# lemidi.net
KiCad netlist of a schematic drawn in EAGLE
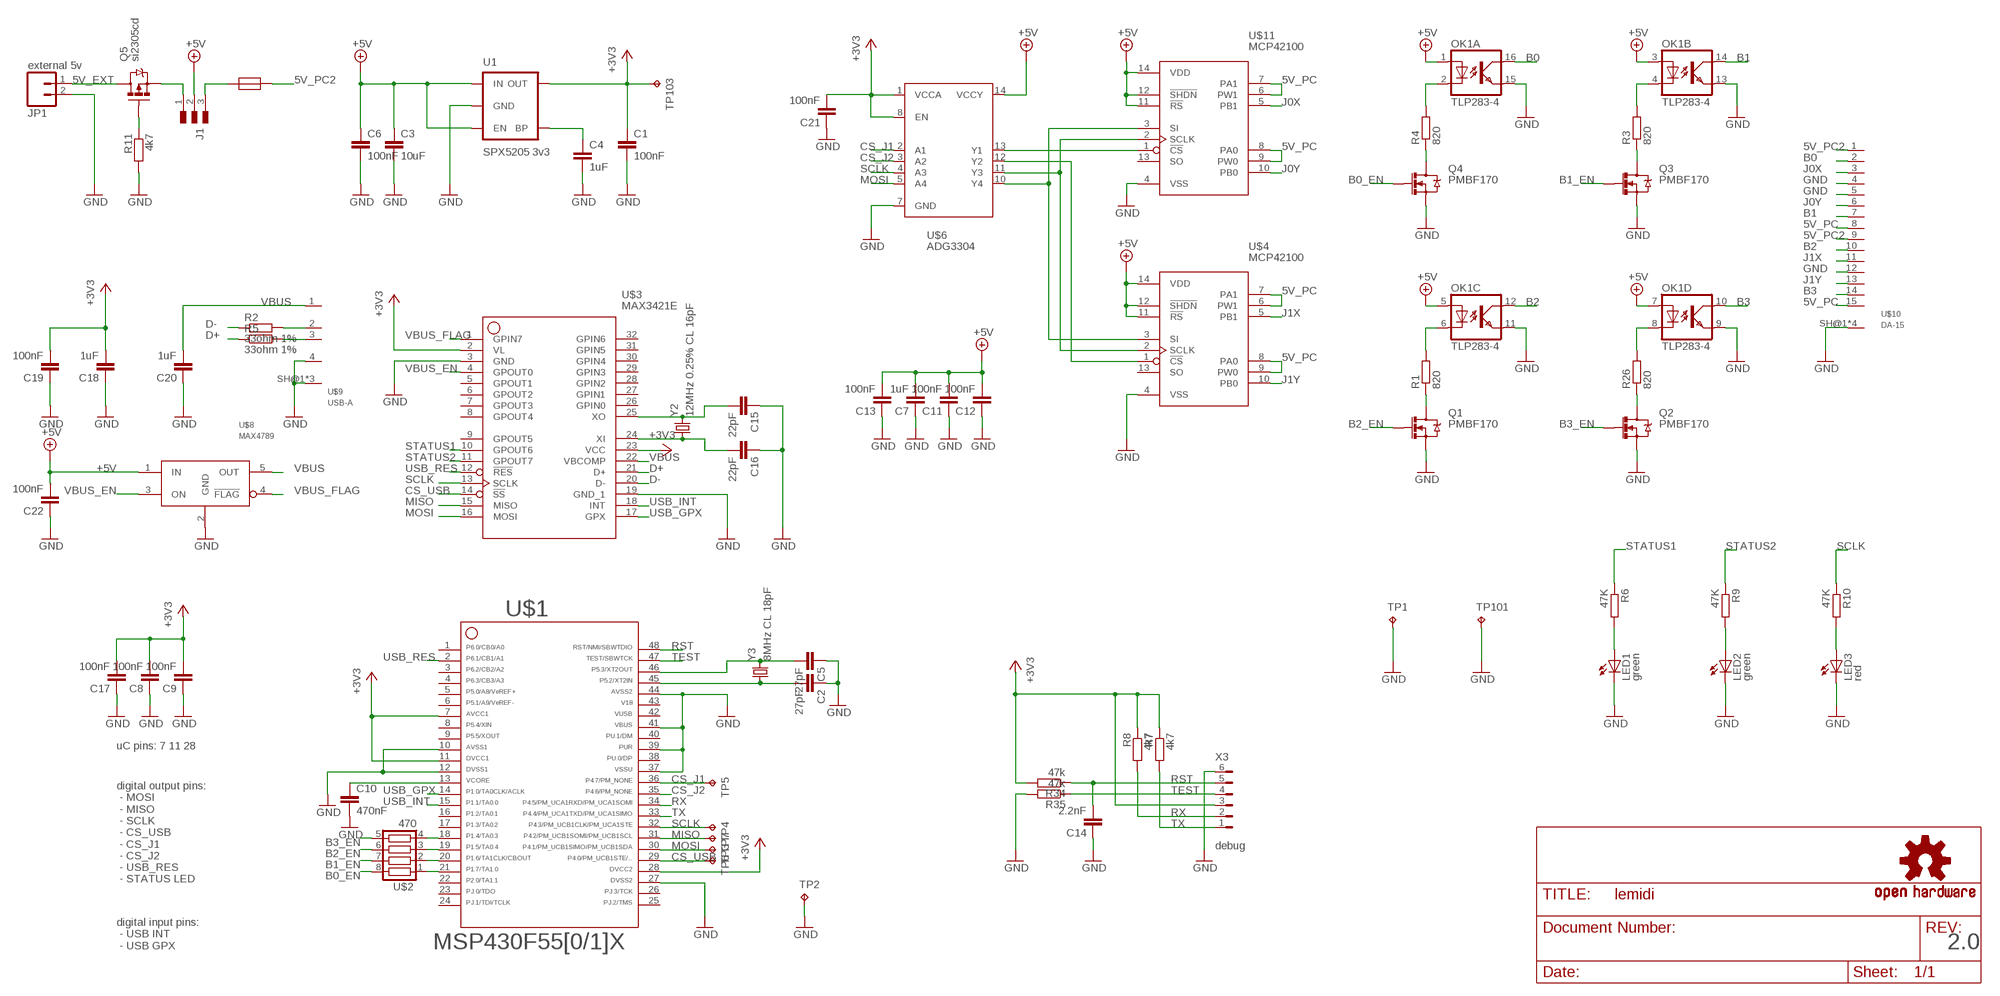
[diagram p0: schematic, sheet 1]

(export (version "E")
  (design (tool "Eeschema 10.0.6"))
  (components
    (comp (ref "C1")
      (value "100nF")
      (footprint "eagle-import:C0805")
      (libsource (lib "eagle-import") (part "C-EUC0805"))
    )
    (comp (ref "C2")
      (value "27pF")
      (footprint "eagle-import:C0805")
      (libsource (lib "eagle-import") (part "C-EUC0805"))
    )
    (comp (ref "C3")
      (value "10uF")
      (footprint "eagle-import:C0805")
      (libsource (lib "eagle-import") (part "C-EUC0805"))
    )
    (comp (ref "C4")
      (value "1uF")
      (footprint "eagle-import:C0805")
      (libsource (lib "eagle-import") (part "C-EUC0805"))
    )
    (comp (ref "C5")
      (value "27pF")
      (footprint "eagle-import:C0805")
      (libsource (lib "eagle-import") (part "C-EUC0805"))
    )
    (comp (ref "C6")
      (value "100nF")
      (footprint "eagle-import:C0805")
      (libsource (lib "eagle-import") (part "C-EUC0805"))
    )
    (comp (ref "C7")
      (value "1uF")
      (footprint "eagle-import:C0805")
      (libsource (lib "eagle-import") (part "C-EUC0805"))
    )
    (comp (ref "C8")
      (value "100nF")
      (footprint "eagle-import:C0805")
      (libsource (lib "eagle-import") (part "C-EUC0805"))
    )
    (comp (ref "C9")
      (value "100nF")
      (footprint "eagle-import:C0805")
      (libsource (lib "eagle-import") (part "C-EUC0805"))
    )
    (comp (ref "C10")
      (value "470nF")
      (footprint "eagle-import:C0805")
      (libsource (lib "eagle-import") (part "C-EUC0805"))
    )
    (comp (ref "C11")
      (value "100nF")
      (footprint "eagle-import:C0805")
      (libsource (lib "eagle-import") (part "C-EUC0805"))
    )
    (comp (ref "C12")
      (value "100nF")
      (footprint "eagle-import:C0805")
      (libsource (lib "eagle-import") (part "C-EUC0805"))
    )
    (comp (ref "C13")
      (value "100nF")
      (footprint "eagle-import:C0805")
      (libsource (lib "eagle-import") (part "C-EUC0805"))
    )
    (comp (ref "C14")
      (value "2.2nF")
      (footprint "eagle-import:C0805")
      (libsource (lib "eagle-import") (part "C-EUC0805"))
    )
    (comp (ref "C15")
      (value "22pF")
      (footprint "eagle-import:C0805")
      (libsource (lib "eagle-import") (part "C-EUC0805"))
    )
    (comp (ref "C16")
      (value "22pF")
      (footprint "eagle-import:C0805")
      (libsource (lib "eagle-import") (part "C-EUC0805"))
    )
    (comp (ref "C17")
      (value "100nF")
      (footprint "eagle-import:C0805")
      (libsource (lib "eagle-import") (part "C-EUC0805"))
    )
    (comp (ref "C18")
      (value "1uF")
      (footprint "eagle-import:C0805")
      (libsource (lib "eagle-import") (part "C-EUC0805"))
    )
    (comp (ref "C19")
      (value "100nF")
      (footprint "eagle-import:C0805")
      (libsource (lib "eagle-import") (part "C-EUC0805"))
    )
    (comp (ref "C20")
      (value "1uF")
      (footprint "eagle-import:C0805")
      (libsource (lib "eagle-import") (part "C-EUC0805"))
    )
    (comp (ref "C21")
      (value "100nF")
      (footprint "eagle-import:C0805")
      (libsource (lib "eagle-import") (part "C-EUC0805"))
    )
    (comp (ref "C22")
      (value "100nF")
      (footprint "eagle-import:C0805")
      (libsource (lib "eagle-import") (part "C-EUC0805"))
    )
    (comp (ref "J1")
      (value "SJ_3P")
      (footprint "eagle-import:SJ_3P")
      (libsource (lib "eagle-import") (part "SJ_3P"))
    )
    (comp (ref "JP1")
      (value "external 5v")
      (footprint "eagle-import:1X02")
      (libsource (lib "eagle-import") (part "M02PTH"))
    )
    (comp (ref "LED1")
      (value "green")
      (footprint "eagle-import:CHIPLED_0805")
      (libsource (lib "eagle-import") (part "LEDCHIPLED_0805"))
    )
    (comp (ref "LED2")
      (value "green")
      (footprint "eagle-import:CHIPLED_0805")
      (libsource (lib "eagle-import") (part "LEDCHIPLED_0805"))
    )
    (comp (ref "LED3")
      (value "red")
      (footprint "eagle-import:CHIPLED_0805")
      (libsource (lib "eagle-import") (part "LEDCHIPLED_0805"))
    )
    (comp (ref "OK1")
      (value "TLP283-4")
      (footprint "eagle-import:MINI-FLAT-16")
      (libsource (lib "eagle-import") (part "TLP283-4"))
    )
    (comp (ref "Q1")
      (value "PMBF170")
      (footprint "eagle-import:SOT23-3")
      (libsource (lib "eagle-import") (part "MOSFET-NCHANNEL_SOT23-3"))
    )
    (comp (ref "Q2")
      (value "PMBF170")
      (footprint "eagle-import:SOT23-3")
      (libsource (lib "eagle-import") (part "MOSFET-NCHANNEL_SOT23-3"))
    )
    (comp (ref "Q3")
      (value "PMBF170")
      (footprint "eagle-import:SOT23-3")
      (libsource (lib "eagle-import") (part "MOSFET-NCHANNEL_SOT23-3"))
    )
    (comp (ref "Q4")
      (value "PMBF170")
      (footprint "eagle-import:SOT23-3")
      (libsource (lib "eagle-import") (part "MOSFET-NCHANNEL_SOT23-3"))
    )
    (comp (ref "Q5")
      (value "si2305cd")
      (footprint "eagle-import:SOT23-3_POWER")
      (libsource (lib "eagle-import") (part "MOSFET-PCHANNELSMD_POWER"))
    )
    (comp (ref "R1")
      (value "820")
      (footprint "eagle-import:R0805W")
      (libsource (lib "eagle-import") (part "R-EU_R0805W"))
    )
    (comp (ref "R2")
      (value "33ohm 1%")
      (footprint "eagle-import:R0805W")
      (libsource (lib "eagle-import") (part "R-EU_R0805W"))
    )
    (comp (ref "R3")
      (value "820")
      (footprint "eagle-import:R0805W")
      (libsource (lib "eagle-import") (part "R-EU_R0805W"))
    )
    (comp (ref "R4")
      (value "820")
      (footprint "eagle-import:R0805W")
      (libsource (lib "eagle-import") (part "R-EU_R0805W"))
    )
    (comp (ref "R5")
      (value "33ohm 1%")
      (footprint "eagle-import:R0805W")
      (libsource (lib "eagle-import") (part "R-EU_R0805W"))
    )
    (comp (ref "R6")
      (value "47K")
      (footprint "eagle-import:R0805W")
      (libsource (lib "eagle-import") (part "R-EU_R0805W"))
    )
    (comp (ref "R7")
      (value "4k7")
      (footprint "eagle-import:R0805W")
      (libsource (lib "eagle-import") (part "R-EU_R0805W"))
    )
    (comp (ref "R8")
      (value "4k7")
      (footprint "eagle-import:R0805W")
      (libsource (lib "eagle-import") (part "R-EU_R0805W"))
    )
    (comp (ref "R9")
      (value "47K")
      (footprint "eagle-import:R0805W")
      (libsource (lib "eagle-import") (part "R-EU_R0805W"))
    )
    (comp (ref "R10")
      (value "47K")
      (footprint "eagle-import:R0805W")
      (libsource (lib "eagle-import") (part "R-EU_R0805W"))
    )
    (comp (ref "R11")
      (value "4k7")
      (footprint "eagle-import:R0805W")
      (libsource (lib "eagle-import") (part "R-EU_R0805W"))
    )
    (comp (ref "R26")
      (value "820")
      (footprint "eagle-import:R0805W")
      (libsource (lib "eagle-import") (part "R-EU_R0805W"))
    )
    (comp (ref "R34")
      (value "47k")
      (footprint "eagle-import:R0805W")
      (libsource (lib "eagle-import") (part "R-EU_R0805W"))
    )
    (comp (ref "R35")
      (value "47k")
      (footprint "eagle-import:R0805W")
      (libsource (lib "eagle-import") (part "R-EU_R0805W"))
    )
    (comp (ref "TP1")
      (value "TPTP12R")
      (footprint "eagle-import:TP12R")
      (libsource (lib "eagle-import") (part "TPTP12R"))
    )
    (comp (ref "TP2")
      (value "TPTP12R")
      (footprint "eagle-import:TP12R")
      (libsource (lib "eagle-import") (part "TPTP12R"))
    )
    (comp (ref "TP3")
      (value "TPTP12R")
      (footprint "eagle-import:TP12R")
      (libsource (lib "eagle-import") (part "TPTP12R"))
    )
    (comp (ref "TP4")
      (value "TPTP12R")
      (footprint "eagle-import:TP12R")
      (libsource (lib "eagle-import") (part "TPTP12R"))
    )
    (comp (ref "TP5")
      (value "TPTP12R")
      (footprint "eagle-import:TP12R")
      (libsource (lib "eagle-import") (part "TPTP12R"))
    )
    (comp (ref "TP6")
      (value "TPTP12R")
      (footprint "eagle-import:TP12R")
      (libsource (lib "eagle-import") (part "TPTP12R"))
    )
    (comp (ref "TP7")
      (value "TPTP12R")
      (footprint "eagle-import:TP12R")
      (libsource (lib "eagle-import") (part "TPTP12R"))
    )
    (comp (ref "TP101")
      (value "TPTP12R")
      (footprint "eagle-import:TP12R")
      (libsource (lib "eagle-import") (part "TPTP12R"))
    )
    (comp (ref "TP103")
      (value "TPTP12R")
      (footprint "eagle-import:TP12R")
      (libsource (lib "eagle-import") (part "TPTP12R"))
    )
    (comp (ref "U$1")
      (value "MSP430F5510")
      (footprint "eagle-import:PT48")
      (libsource (lib "eagle-import") (part "F55[0/1]X---PT48"))
    )
    (comp (ref "U$2")
      (value "470")
      (footprint "eagle-import:YC164")
      (libsource (lib "eagle-import") (part "RES_ARR"))
    )
    (comp (ref "U$3")
      (value "MAX3421E")
      (footprint "eagle-import:TQFP32")
      (libsource (lib "eagle-import") (part "MAX3421E"))
    )
    (comp (ref "U$4")
      (value "MCP42100")
      (footprint "eagle-import:SO-14")
      (libsource (lib "eagle-import") (part "MCP42XX"))
    )
    (comp (ref "U$6")
      (value "ADG3304")
      (footprint "eagle-import:TSSOP14")
      (libsource (lib "eagle-import") (part "ADG3304"))
    )
    (comp (ref "U$7")
      (value "OSHW-LOGOM")
      (footprint "eagle-import:OSHW-LOGO-M")
      (libsource (lib "eagle-import") (part "OSHW-LOGOM"))
    )
    (comp (ref "U$8")
      (value "MAX4789")
      (footprint "eagle-import:SOT23-5")
      (libsource (lib "eagle-import") (part "MAX4789"))
    )
    (comp (ref "U$9")
      (value "USB-A")
      (footprint "eagle-import:UBA-4R-D14T-4D")
      (libsource (lib "eagle-import") (part "UBA-4R-D14T-4D"))
    )
    (comp (ref "U$10")
      (value "DA-15")
      (footprint "eagle-import:ADAM_TECH_D-SUB_15")
      (libsource (lib "eagle-import") (part "ADAM_TECH-DSUB_DA-15"))
    )
    (comp (ref "U$11")
      (value "MCP42100")
      (footprint "eagle-import:SO-14")
      (libsource (lib "eagle-import") (part "MCP42XX"))
    )
    (comp (ref "U$12")
      (value "RESETTABLE_1210")
      (footprint "eagle-import:1210")
      (libsource (lib "eagle-import") (part "RESETTABLE_1210"))
    )
    (comp (ref "U1")
      (value "SPX5205 3v3")
      (footprint "eagle-import:SOT23-5")
      (libsource (lib "eagle-import") (part "V_REG_LDOSMD"))
    )
    (comp (ref "X3")
      (value "debug")
      (footprint "eagle-import:0530480610")
      (libsource (lib "eagle-import") (part "MOLEX_6HORIZONTAL"))
    )
    (comp (ref "Y2")
      (value "12MHz 0.25% CL 16pF")
      (footprint "eagle-import:CRYSTAL-SMD-11.4X4.35")
      (libsource (lib "eagle-import") (part "CRYSTAL"))
    )
    (comp (ref "Y3")
      (value "8MHz CL 18pF")
      (footprint "eagle-import:CRYSTAL-SMD-11.4X4.35")
      (libsource (lib "eagle-import") (part "CRYSTAL"))
    )
  )
  (nets
    (net (code "1") (name "+3V3") (class "Default")
      (node (ref "C1") (pin "1") (pinfunction "1_1") (pintype "passive"))
      (node (ref "C17") (pin "2") (pinfunction "2_2") (pintype "passive"))
      (node (ref "C18") (pin "2") (pinfunction "2_2") (pintype "passive"))
      (node (ref "C19") (pin "2") (pinfunction "2_2") (pintype "passive"))
      (node (ref "C21") (pin "2") (pinfunction "2_2") (pintype "passive"))
      (node (ref "C8") (pin "2") (pinfunction "2_2") (pintype "passive"))
      (node (ref "C9") (pin "2") (pinfunction "2_2") (pintype "passive"))
      (node (ref "R34") (pin "2") (pinfunction "2_2") (pintype "passive"))
      (node (ref "R7") (pin "1") (pinfunction "1_1") (pintype "passive"))
      (node (ref "R8") (pin "1") (pinfunction "1_1") (pintype "passive"))
      (node (ref "TP103") (pin "TP") (pinfunction "TP_TP") (pintype "input"))
      (node (ref "U$1") (pin "11") (pinfunction "11_11") (pintype "power_in"))
      (node (ref "U$1") (pin "28") (pinfunction "28_28") (pintype "power_in"))
      (node (ref "U$1") (pin "7") (pinfunction "7_7") (pintype "power_in"))
      (node (ref "U$3") (pin "2") (pinfunction "VL_2") (pintype "input"))
      (node (ref "U$3") (pin "23") (pinfunction "VCC_23") (pintype "bidirectional"))
      (node (ref "U$6") (pin "1") (pinfunction "VCCA_1") (pintype "bidirectional"))
      (node (ref "U$6") (pin "8") (pinfunction "EN_8") (pintype "bidirectional"))
      (node (ref "U1") (pin "5") (pinfunction "OUT_5") (pintype "passive"))
      (node (ref "X3") (pin "3") (pinfunction "4_3") (pintype "passive"))
    )
    (net (code "2") (name "+5V") (class "Default")
      (node (ref "C11") (pin "2") (pinfunction "2_2") (pintype "passive"))
      (node (ref "C12") (pin "2") (pinfunction "2_2") (pintype "passive"))
      (node (ref "C13") (pin "2") (pinfunction "2_2") (pintype "passive"))
      (node (ref "C22") (pin "2") (pinfunction "2_2") (pintype "passive"))
      (node (ref "C3") (pin "1") (pinfunction "1_1") (pintype "passive"))
      (node (ref "C6") (pin "1") (pinfunction "1_1") (pintype "passive"))
      (node (ref "C7") (pin "2") (pinfunction "2_2") (pintype "passive"))
      (node (ref "J1") (pin "2") (pinfunction "2_2") (pintype "passive"))
      (node (ref "OK1") (pin "1") (pinfunction "A_1") (pintype "passive"))
      (node (ref "OK1") (pin "3") (pinfunction "A_3") (pintype "passive"))
      (node (ref "OK1") (pin "5") (pinfunction "A_5") (pintype "passive"))
      (node (ref "OK1") (pin "7") (pinfunction "A_7") (pintype "passive"))
      (node (ref "U$11") (pin "11") (pinfunction "~{RS}_11") (pintype "bidirectional"))
      (node (ref "U$11") (pin "12") (pinfunction "~{SHDN}_12") (pintype "bidirectional"))
      (node (ref "U$11") (pin "14") (pinfunction "VDD_14") (pintype "bidirectional"))
      (node (ref "U$4") (pin "11") (pinfunction "~{RS}_11") (pintype "bidirectional"))
      (node (ref "U$4") (pin "12") (pinfunction "~{SHDN}_12") (pintype "bidirectional"))
      (node (ref "U$4") (pin "14") (pinfunction "VDD_14") (pintype "bidirectional"))
      (node (ref "U$6") (pin "14") (pinfunction "VCCY_14") (pintype "bidirectional"))
      (node (ref "U$8") (pin "1") (pinfunction "IN_1") (pintype "power_in"))
      (node (ref "U1") (pin "1") (pinfunction "IN_1") (pintype "input"))
      (node (ref "U1") (pin "3") (pinfunction "EN_3") (pintype "input"))
    )
    (net (code "3") (name "/5V_EXT") (class "Default")
      (node (ref "JP1") (pin "1") (pinfunction "1_1") (pintype "passive"))
      (node (ref "Q5") (pin "3") (pinfunction "D_3") (pintype "passive"))
    )
    (net (code "4") (name "/5V_PC") (class "Default")
      (node (ref "U$10") (pin "15") (pinfunction "15_15") (pintype "bidirectional"))
      (node (ref "U$10") (pin "8") (pinfunction "8_8") (pintype "bidirectional"))
      (node (ref "U$11") (pin "6") (pinfunction "PW1_6") (pintype "bidirectional"))
      (node (ref "U$11") (pin "7") (pinfunction "PA1_7") (pintype "bidirectional"))
      (node (ref "U$11") (pin "8") (pinfunction "PA0_8") (pintype "bidirectional"))
      (node (ref "U$11") (pin "9") (pinfunction "PW0_9") (pintype "bidirectional"))
      (node (ref "U$4") (pin "6") (pinfunction "PW1_6") (pintype "bidirectional"))
      (node (ref "U$4") (pin "7") (pinfunction "PA1_7") (pintype "bidirectional"))
      (node (ref "U$4") (pin "8") (pinfunction "PA0_8") (pintype "bidirectional"))
      (node (ref "U$4") (pin "9") (pinfunction "PW0_9") (pintype "bidirectional"))
    )
    (net (code "5") (name "/5V_PC2") (class "Default")
      (node (ref "U$10") (pin "1") (pinfunction "1_1") (pintype "bidirectional"))
      (node (ref "U$10") (pin "9") (pinfunction "9_9") (pintype "bidirectional"))
      (node (ref "U$12") (pin "P$2") (pinfunction "P$2_P$2") (pintype "bidirectional"))
    )
    (net (code "6") (name "/42") (class "Default")
      (node (ref "U$1") (pin "42") (pinfunction "42_42") (pintype "power_in"))
    )
    (net (code "7") (name "/43") (class "Default")
      (node (ref "U$1") (pin "43") (pinfunction "43_43") (pintype "power_in"))
    )
    (net (code "8") (name "/B0") (class "Default")
      (node (ref "OK1") (pin "16") (pinfunction "COL_16") (pintype "passive"))
      (node (ref "U$10") (pin "2") (pinfunction "2_2") (pintype "bidirectional"))
    )
    (net (code "9") (name "/B0_EN") (class "Default")
      (node (ref "Q4") (pin "1") (pinfunction "G_1") (pintype "passive"))
      (node (ref "U$2") (pin "8") (pinfunction "8_8") (pintype "passive"))
    )
    (net (code "10") (name "/B1") (class "Default")
      (node (ref "OK1") (pin "14") (pinfunction "COL_14") (pintype "passive"))
      (node (ref "U$10") (pin "7") (pinfunction "7_7") (pintype "bidirectional"))
    )
    (net (code "11") (name "/B1_EN") (class "Default")
      (node (ref "Q3") (pin "1") (pinfunction "G_1") (pintype "passive"))
      (node (ref "U$2") (pin "7") (pinfunction "7_7") (pintype "passive"))
    )
    (net (code "12") (name "/B2") (class "Default")
      (node (ref "OK1") (pin "12") (pinfunction "COL_12") (pintype "passive"))
      (node (ref "U$10") (pin "10") (pinfunction "10_10") (pintype "bidirectional"))
    )
    (net (code "13") (name "/B2_EN") (class "Default")
      (node (ref "Q1") (pin "1") (pinfunction "G_1") (pintype "passive"))
      (node (ref "U$2") (pin "6") (pinfunction "6_6") (pintype "passive"))
    )
    (net (code "14") (name "/B3") (class "Default")
      (node (ref "OK1") (pin "10") (pinfunction "COL_10") (pintype "passive"))
      (node (ref "U$10") (pin "14") (pinfunction "14_14") (pintype "bidirectional"))
    )
    (net (code "15") (name "/B3_EN") (class "Default")
      (node (ref "Q2") (pin "1") (pinfunction "G_1") (pintype "passive"))
      (node (ref "U$2") (pin "5") (pinfunction "5_5") (pintype "passive"))
    )
    (net (code "16") (name "/CS_J1") (class "Default")
      (node (ref "TP5") (pin "TP") (pinfunction "TP_TP") (pintype "input"))
      (node (ref "U$1") (pin "36") (pinfunction "36_36") (pintype "bidirectional"))
      (node (ref "U$6") (pin "2") (pinfunction "A1_2") (pintype "bidirectional"))
    )
    (net (code "17") (name "/CS_J2") (class "Default")
      (node (ref "U$1") (pin "35") (pinfunction "35_35") (pintype "bidirectional"))
      (node (ref "U$6") (pin "3") (pinfunction "A2_3") (pintype "bidirectional"))
    )
    (net (code "18") (name "/CS_USB") (class "Default")
      (node (ref "TP6") (pin "TP") (pinfunction "TP_TP") (pintype "input"))
      (node (ref "U$1") (pin "29") (pinfunction "29_29") (pintype "bidirectional"))
      (node (ref "U$3") (pin "14") (pinfunction "~{SS}_14") (pintype "input"))
    )
    (net (code "19") (name "/D+") (class "Default")
      (node (ref "R5") (pin "1") (pinfunction "1_1") (pintype "passive"))
      (node (ref "U$3") (pin "21") (pinfunction "D+_21") (pintype "bidirectional"))
    )
    (net (code "20") (name "/D-") (class "Default")
      (node (ref "R2") (pin "1") (pinfunction "1_1") (pintype "passive"))
      (node (ref "U$3") (pin "20") (pinfunction "D-_20") (pintype "bidirectional"))
    )
    (net (code "21") (name "/J0X") (class "Default")
      (node (ref "U$10") (pin "3") (pinfunction "3_3") (pintype "bidirectional"))
      (node (ref "U$11") (pin "5") (pinfunction "PB1_5") (pintype "bidirectional"))
    )
    (net (code "22") (name "/J0Y") (class "Default")
      (node (ref "U$10") (pin "6") (pinfunction "6_6") (pintype "bidirectional"))
      (node (ref "U$11") (pin "10") (pinfunction "PB0_10") (pintype "bidirectional"))
    )
    (net (code "23") (name "/J1X") (class "Default")
      (node (ref "U$10") (pin "11") (pinfunction "11_11") (pintype "bidirectional"))
      (node (ref "U$4") (pin "5") (pinfunction "PB1_5") (pintype "bidirectional"))
    )
    (net (code "24") (name "/J1Y") (class "Default")
      (node (ref "U$10") (pin "13") (pinfunction "13_13") (pintype "bidirectional"))
      (node (ref "U$4") (pin "10") (pinfunction "PB0_10") (pintype "bidirectional"))
    )
    (net (code "25") (name "/MISO") (class "Default")
      (node (ref "TP7") (pin "TP") (pinfunction "TP_TP") (pintype "input"))
      (node (ref "U$1") (pin "31") (pinfunction "31_31") (pintype "bidirectional"))
      (node (ref "U$3") (pin "15") (pinfunction "MISO_15") (pintype "output"))
    )
    (net (code "26") (name "/MOSI") (class "Default")
      (node (ref "TP3") (pin "TP") (pinfunction "TP_TP") (pintype "input"))
      (node (ref "U$1") (pin "30") (pinfunction "30_30") (pintype "bidirectional"))
      (node (ref "U$3") (pin "16") (pinfunction "MOSI_16") (pintype "bidirectional"))
      (node (ref "U$6") (pin "5") (pinfunction "A4_5") (pintype "bidirectional"))
    )
    (net (code "27") (name "/RST") (class "Default")
      (node (ref "C14") (pin "2") (pinfunction "2_2") (pintype "passive"))
      (node (ref "R34") (pin "1") (pinfunction "1_1") (pintype "passive"))
      (node (ref "U$1") (pin "48") (pinfunction "48_48") (pintype "bidirectional"))
      (node (ref "X3") (pin "5") (pinfunction "2_5") (pintype "passive"))
    )
    (net (code "28") (name "/RX") (class "Default")
      (node (ref "R8") (pin "2") (pinfunction "2_2") (pintype "passive"))
      (node (ref "U$1") (pin "34") (pinfunction "34_34") (pintype "bidirectional"))
      (node (ref "X3") (pin "2") (pinfunction "5_2") (pintype "passive"))
    )
    (net (code "29") (name "/SCLK") (class "Default")
      (node (ref "R10") (pin "1") (pinfunction "1_1") (pintype "passive"))
      (node (ref "TP4") (pin "TP") (pinfunction "TP_TP") (pintype "input"))
      (node (ref "U$1") (pin "32") (pinfunction "32_32") (pintype "bidirectional"))
      (node (ref "U$3") (pin "13") (pinfunction "SCLK_13") (pintype "input"))
      (node (ref "U$6") (pin "4") (pinfunction "A3_4") (pintype "bidirectional"))
    )
    (net (code "30") (name "/STATUS1") (class "Default")
      (node (ref "R6") (pin "1") (pinfunction "1_1") (pintype "passive"))
      (node (ref "U$3") (pin "10") (pinfunction "GPOUT6_10") (pintype "output"))
    )
    (net (code "31") (name "/STATUS2") (class "Default")
      (node (ref "R9") (pin "1") (pinfunction "1_1") (pintype "passive"))
      (node (ref "U$3") (pin "11") (pinfunction "GPOUT7_11") (pintype "output"))
    )
    (net (code "32") (name "/TEST") (class "Default")
      (node (ref "R35") (pin "1") (pinfunction "1_1") (pintype "passive"))
      (node (ref "U$1") (pin "47") (pinfunction "47_47") (pintype "input"))
      (node (ref "X3") (pin "4") (pinfunction "3_4") (pintype "passive"))
    )
    (net (code "33") (name "/TX") (class "Default")
      (node (ref "R7") (pin "2") (pinfunction "2_2") (pintype "passive"))
      (node (ref "U$1") (pin "33") (pinfunction "33_33") (pintype "bidirectional"))
      (node (ref "X3") (pin "1") (pinfunction "6_1") (pintype "passive"))
    )
    (net (code "34") (name "/USB_GPX") (class "Default")
      (node (ref "U$1") (pin "14") (pinfunction "14_14") (pintype "bidirectional"))
      (node (ref "U$3") (pin "17") (pinfunction "GPX_17") (pintype "output"))
    )
    (net (code "35") (name "/USB_INT") (class "Default")
      (node (ref "U$1") (pin "15") (pinfunction "15_15") (pintype "bidirectional"))
      (node (ref "U$3") (pin "18") (pinfunction "INT_18") (pintype "output"))
    )
    (net (code "36") (name "/USB_RES") (class "Default")
      (node (ref "U$1") (pin "2") (pinfunction "2_2") (pintype "bidirectional"))
      (node (ref "U$3") (pin "12") (pinfunction "~{RES}_12") (pintype "input"))
    )
    (net (code "37") (name "/VBUS") (class "Default")
      (node (ref "C20") (pin "2") (pinfunction "2_2") (pintype "passive"))
      (node (ref "U$3") (pin "22") (pinfunction "VBCOMP_22") (pintype "input"))
      (node (ref "U$8") (pin "5") (pinfunction "OUT_5") (pintype "power_in"))
      (node (ref "U$9") (pin "1") (pinfunction "1_1") (pintype "bidirectional"))
    )
    (net (code "38") (name "/VBUS_EN") (class "Default")
      (node (ref "U$3") (pin "4") (pinfunction "GPOUT0_4") (pintype "output"))
      (node (ref "U$8") (pin "3") (pinfunction "ON_3") (pintype "input"))
    )
    (net (code "39") (name "/VBUS_FLAG") (class "Default")
      (node (ref "U$3") (pin "1") (pinfunction "GPIN7_1") (pintype "input"))
      (node (ref "U$8") (pin "4") (pinfunction "~{FLAG}_4") (pintype "output"))
    )
    (net (code "40") (name "GND") (class "Default")
      (node (ref "C1") (pin "2") (pinfunction "2_2") (pintype "passive"))
      (node (ref "C10") (pin "2") (pinfunction "2_2") (pintype "passive"))
      (node (ref "C11") (pin "1") (pinfunction "1_1") (pintype "passive"))
      (node (ref "C12") (pin "1") (pinfunction "1_1") (pintype "passive"))
      (node (ref "C13") (pin "1") (pinfunction "1_1") (pintype "passive"))
      (node (ref "C14") (pin "1") (pinfunction "1_1") (pintype "passive"))
      (node (ref "C15") (pin "1") (pinfunction "1_1") (pintype "passive"))
      (node (ref "C16") (pin "1") (pinfunction "1_1") (pintype "passive"))
      (node (ref "C17") (pin "1") (pinfunction "1_1") (pintype "passive"))
      (node (ref "C18") (pin "1") (pinfunction "1_1") (pintype "passive"))
      (node (ref "C19") (pin "1") (pinfunction "1_1") (pintype "passive"))
      (node (ref "C2") (pin "1") (pinfunction "1_1") (pintype "passive"))
      (node (ref "C20") (pin "1") (pinfunction "1_1") (pintype "passive"))
      (node (ref "C21") (pin "1") (pinfunction "1_1") (pintype "passive"))
      (node (ref "C22") (pin "1") (pinfunction "1_1") (pintype "passive"))
      (node (ref "C3") (pin "2") (pinfunction "2_2") (pintype "passive"))
      (node (ref "C4") (pin "2") (pinfunction "2_2") (pintype "passive"))
      (node (ref "C5") (pin "1") (pinfunction "1_1") (pintype "passive"))
      (node (ref "C6") (pin "2") (pinfunction "2_2") (pintype "passive"))
      (node (ref "C7") (pin "1") (pinfunction "1_1") (pintype "passive"))
      (node (ref "C8") (pin "1") (pinfunction "1_1") (pintype "passive"))
      (node (ref "C9") (pin "1") (pinfunction "1_1") (pintype "passive"))
      (node (ref "JP1") (pin "2") (pinfunction "2_2") (pintype "passive"))
      (node (ref "LED1") (pin "C") (pinfunction "C_C") (pintype "passive"))
      (node (ref "LED2") (pin "C") (pinfunction "C_C") (pintype "passive"))
      (node (ref "LED3") (pin "C") (pinfunction "C_C") (pintype "passive"))
      (node (ref "OK1") (pin "11") (pinfunction "EMIT_11") (pintype "passive"))
      (node (ref "OK1") (pin "13") (pinfunction "EMIT_13") (pintype "passive"))
      (node (ref "OK1") (pin "15") (pinfunction "EMIT_15") (pintype "passive"))
      (node (ref "OK1") (pin "9") (pinfunction "EMIT_9") (pintype "passive"))
      (node (ref "Q1") (pin "2") (pinfunction "S_2") (pintype "passive"))
      (node (ref "Q2") (pin "2") (pinfunction "S_2") (pintype "passive"))
      (node (ref "Q3") (pin "2") (pinfunction "S_2") (pintype "passive"))
      (node (ref "Q4") (pin "2") (pinfunction "S_2") (pintype "passive"))
      (node (ref "R11") (pin "2") (pinfunction "2_2") (pintype "passive"))
      (node (ref "R35") (pin "2") (pinfunction "2_2") (pintype "passive"))
      (node (ref "TP1") (pin "TP") (pinfunction "TP_TP") (pintype "input"))
      (node (ref "TP101") (pin "TP") (pinfunction "TP_TP") (pintype "input"))
      (node (ref "TP2") (pin "TP") (pinfunction "TP_TP") (pintype "input"))
      (node (ref "U$1") (pin "10") (pinfunction "10_10") (pintype "power_in"))
      (node (ref "U$1") (pin "12") (pinfunction "12_12") (pintype "power_in"))
      (node (ref "U$1") (pin "27") (pinfunction "27_27") (pintype "power_in"))
      (node (ref "U$1") (pin "37") (pinfunction "37_37") (pintype "power_in"))
      (node (ref "U$1") (pin "39") (pinfunction "39_39") (pintype "bidirectional"))
      (node (ref "U$1") (pin "41") (pinfunction "41_41") (pintype "power_in"))
      (node (ref "U$1") (pin "44") (pinfunction "44_44") (pintype "power_in"))
      (node (ref "U$10") (pin "12") (pinfunction "12_12") (pintype "bidirectional"))
      (node (ref "U$10") (pin "4") (pinfunction "4_4") (pintype "bidirectional"))
      (node (ref "U$10") (pin "5") (pinfunction "5_5") (pintype "bidirectional"))
      (node (ref "U$10") (pin "SH@1") (pinfunction "SHIELD_SH@1") (pintype "bidirectional"))
      (node (ref "U$10") (pin "SH@2") (pinfunction "SHIELD_SH@2") (pintype "bidirectional"))
      (node (ref "U$10") (pin "SH@3") (pinfunction "SHIELD_SH@3") (pintype "bidirectional"))
      (node (ref "U$10") (pin "SH@4") (pinfunction "SHIELD_SH@4") (pintype "bidirectional"))
      (node (ref "U$11") (pin "4") (pinfunction "VSS_4") (pintype "bidirectional"))
      (node (ref "U$3") (pin "19") (pinfunction "GND_1_19") (pintype "bidirectional"))
      (node (ref "U$3") (pin "3") (pinfunction "GND_3") (pintype "bidirectional"))
      (node (ref "U$4") (pin "4") (pinfunction "VSS_4") (pintype "bidirectional"))
      (node (ref "U$6") (pin "7") (pinfunction "GND_7") (pintype "bidirectional"))
      (node (ref "U$8") (pin "2") (pinfunction "GND_2") (pintype "bidirectional"))
      (node (ref "U$9") (pin "4") (pinfunction "4_4") (pintype "bidirectional"))
      (node (ref "U$9") (pin "SH@1") (pinfunction "SH_SH@1") (pintype "bidirectional"))
      (node (ref "U$9") (pin "SH@2") (pinfunction "SH_SH@2") (pintype "bidirectional"))
      (node (ref "U$9") (pin "SH@3") (pinfunction "SH_SH@3") (pintype "bidirectional"))
      (node (ref "U1") (pin "2") (pinfunction "GND_2") (pintype "input"))
      (node (ref "X3") (pin "6") (pinfunction "1_6") (pintype "passive"))
    )
    (net (code "41") (name "Net-(C2-Pad2)") (class "Default")
      (node (ref "C2") (pin "2") (pinfunction "2_2") (pintype "passive"))
      (node (ref "U$1") (pin "45") (pinfunction "45_45") (pintype "bidirectional"))
      (node (ref "Y3") (pin "1") (pinfunction "1_1") (pintype "passive"))
    )
    (net (code "42") (name "Net-(C5-Pad2)") (class "Default")
      (node (ref "C5") (pin "2") (pinfunction "2_2") (pintype "passive"))
      (node (ref "U$1") (pin "46") (pinfunction "46_46") (pintype "power_in"))
      (node (ref "Y3") (pin "2") (pinfunction "2_2") (pintype "passive"))
    )
    (net (code "43") (name "Net-(C10-Pad1)") (class "Default")
      (node (ref "C10") (pin "1") (pinfunction "1_1") (pintype "passive"))
      (node (ref "U$1") (pin "13") (pinfunction "13_13") (pintype "power_in"))
    )
    (net (code "44") (name "Net-(J1-Pad3)") (class "Default")
      (node (ref "J1") (pin "3") (pinfunction "3_3") (pintype "passive"))
      (node (ref "U$12") (pin "P$1") (pinfunction "P$1_P$1") (pintype "bidirectional"))
    )
    (net (code "45") (name "Net-(LED1-PadA)") (class "Default")
      (node (ref "LED1") (pin "A") (pinfunction "A_A") (pintype "passive"))
      (node (ref "R6") (pin "2") (pinfunction "2_2") (pintype "passive"))
    )
    (net (code "46") (name "Net-(LED2-PadA)") (class "Default")
      (node (ref "LED2") (pin "A") (pinfunction "A_A") (pintype "passive"))
      (node (ref "R9") (pin "2") (pinfunction "2_2") (pintype "passive"))
    )
    (net (code "47") (name "Net-(LED3-PadA)") (class "Default")
      (node (ref "LED3") (pin "A") (pinfunction "A_A") (pintype "passive"))
      (node (ref "R10") (pin "2") (pinfunction "2_2") (pintype "passive"))
    )
    (net (code "48") (name "Net-(OK1A-C)") (class "Default")
      (node (ref "OK1") (pin "2") (pinfunction "C_2") (pintype "passive"))
      (node (ref "R4") (pin "2") (pinfunction "2_2") (pintype "passive"))
    )
    (net (code "49") (name "Net-(OK1B-C)") (class "Default")
      (node (ref "OK1") (pin "4") (pinfunction "C_4") (pintype "passive"))
      (node (ref "R3") (pin "2") (pinfunction "2_2") (pintype "passive"))
    )
    (net (code "50") (name "Net-(OK1C-C)") (class "Default")
      (node (ref "OK1") (pin "6") (pinfunction "C_6") (pintype "passive"))
      (node (ref "R1") (pin "2") (pinfunction "2_2") (pintype "passive"))
    )
    (net (code "51") (name "Net-(OK1D-C)") (class "Default")
      (node (ref "OK1") (pin "8") (pinfunction "C_8") (pintype "passive"))
      (node (ref "R26") (pin "2") (pinfunction "2_2") (pintype "passive"))
    )
    (net (code "52") (name "Net-(Q1-D)") (class "Default")
      (node (ref "Q1") (pin "3") (pinfunction "D_3") (pintype "passive"))
      (node (ref "R1") (pin "1") (pinfunction "1_1") (pintype "passive"))
    )
    (net (code "53") (name "Net-(Q2-D)") (class "Default")
      (node (ref "Q2") (pin "3") (pinfunction "D_3") (pintype "passive"))
      (node (ref "R26") (pin "1") (pinfunction "1_1") (pintype "passive"))
    )
    (net (code "54") (name "Net-(Q3-D)") (class "Default")
      (node (ref "Q3") (pin "3") (pinfunction "D_3") (pintype "passive"))
      (node (ref "R3") (pin "1") (pinfunction "1_1") (pintype "passive"))
    )
    (net (code "55") (name "Net-(Q4-D)") (class "Default")
      (node (ref "Q4") (pin "3") (pinfunction "D_3") (pintype "passive"))
      (node (ref "R4") (pin "1") (pinfunction "1_1") (pintype "passive"))
    )
    (net (code "56") (name "Net-(Q5-G)") (class "Default")
      (node (ref "Q5") (pin "1") (pinfunction "G_1") (pintype "passive"))
      (node (ref "R11") (pin "1") (pinfunction "1_1") (pintype "passive"))
    )
    (net (code "57") (name "Net-(Q5-S)") (class "Default")
      (node (ref "J1") (pin "1") (pinfunction "1_1") (pintype "passive"))
      (node (ref "Q5") (pin "2") (pinfunction "S_2") (pintype "passive"))
    )
    (net (code "58") (name "Net-(R2-Pad2)") (class "Default")
      (node (ref "R2") (pin "2") (pinfunction "2_2") (pintype "passive"))
      (node (ref "U$9") (pin "2") (pinfunction "2_2") (pintype "bidirectional"))
    )
    (net (code "59") (name "Net-(R5-Pad2)") (class "Default")
      (node (ref "R5") (pin "2") (pinfunction "2_2") (pintype "passive"))
      (node (ref "U$9") (pin "3") (pinfunction "3_3") (pintype "bidirectional"))
    )
    (net (code "60") (name "Net-(U$1-Pad18)") (class "Default")
      (node (ref "U$1") (pin "18") (pinfunction "18_18") (pintype "bidirectional"))
      (node (ref "U$2") (pin "4") (pinfunction "4_4") (pintype "passive"))
    )
    (net (code "61") (name "Net-(U$1-Pad19)") (class "Default")
      (node (ref "U$1") (pin "19") (pinfunction "19_19") (pintype "bidirectional"))
      (node (ref "U$2") (pin "3") (pinfunction "3_3") (pintype "passive"))
    )
    (net (code "62") (name "Net-(U$1-Pad20)") (class "Default")
      (node (ref "U$1") (pin "20") (pinfunction "20_20") (pintype "bidirectional"))
      (node (ref "U$2") (pin "2") (pinfunction "2_2") (pintype "passive"))
    )
    (net (code "63") (name "Net-(U$1-Pad21)") (class "Default")
      (node (ref "U$1") (pin "21") (pinfunction "21_21") (pintype "bidirectional"))
      (node (ref "U$2") (pin "1") (pinfunction "1_1") (pintype "passive"))
    )
    (net (code "64") (name "Net-(U$3-XI)") (class "Default")
      (node (ref "C16") (pin "2") (pinfunction "2_2") (pintype "passive"))
      (node (ref "U$3") (pin "24") (pinfunction "XI_24") (pintype "input"))
      (node (ref "Y2") (pin "1") (pinfunction "1_1") (pintype "passive"))
    )
    (net (code "65") (name "Net-(U$3-XO)") (class "Default")
      (node (ref "C15") (pin "2") (pinfunction "2_2") (pintype "passive"))
      (node (ref "U$3") (pin "25") (pinfunction "XO_25") (pintype "output"))
      (node (ref "Y2") (pin "2") (pinfunction "2_2") (pintype "passive"))
    )
    (net (code "66") (name "Net-(U$4-~{CS})") (class "Default")
      (node (ref "U$4") (pin "1") (pinfunction "~{CS}_1") (pintype "input"))
      (node (ref "U$6") (pin "12") (pinfunction "Y2_12") (pintype "bidirectional"))
    )
    (net (code "67") (name "Net-(U$11-SCLK)") (class "Default")
      (node (ref "U$11") (pin "2") (pinfunction "SCLK_2") (pintype "input"))
      (node (ref "U$4") (pin "2") (pinfunction "SCLK_2") (pintype "input"))
      (node (ref "U$6") (pin "11") (pinfunction "Y3_11") (pintype "bidirectional"))
    )
    (net (code "68") (name "Net-(U$11-SI)") (class "Default")
      (node (ref "U$11") (pin "3") (pinfunction "SI_3") (pintype "input"))
      (node (ref "U$4") (pin "3") (pinfunction "SI_3") (pintype "input"))
      (node (ref "U$6") (pin "10") (pinfunction "Y4_10") (pintype "bidirectional"))
    )
    (net (code "69") (name "Net-(U$11-~{CS})") (class "Default")
      (node (ref "U$11") (pin "1") (pinfunction "~{CS}_1") (pintype "input"))
      (node (ref "U$6") (pin "13") (pinfunction "Y1_13") (pintype "bidirectional"))
    )
    (net (code "70") (name "Net-(U1-BP)") (class "Default")
      (node (ref "C4") (pin "1") (pinfunction "1_1") (pintype "passive"))
      (node (ref "U1") (pin "4") (pinfunction "BP_4") (pintype "input"))
    )
    (net (code "71") (name "unconnected-(U$1-Pad1)") (class "Default")
      (node (ref "U$1") (pin "1") (pinfunction "1_1") (pintype "bidirectional"))
    )
    (net (code "72") (name "unconnected-(U$1-Pad3)") (class "Default")
      (node (ref "U$1") (pin "3") (pinfunction "3_3") (pintype "bidirectional"))
    )
    (net (code "73") (name "unconnected-(U$1-Pad4)") (class "Default")
      (node (ref "U$1") (pin "4") (pinfunction "4_4") (pintype "bidirectional"))
    )
    (net (code "74") (name "unconnected-(U$1-Pad5)") (class "Default")
      (node (ref "U$1") (pin "5") (pinfunction "5_5") (pintype "bidirectional"))
    )
    (net (code "75") (name "unconnected-(U$1-Pad6)") (class "Default")
      (node (ref "U$1") (pin "6") (pinfunction "6_6") (pintype "bidirectional"))
    )
    (net (code "76") (name "unconnected-(U$1-Pad8)") (class "Default")
      (node (ref "U$1") (pin "8") (pinfunction "8_8") (pintype "bidirectional"))
    )
    (net (code "77") (name "unconnected-(U$1-Pad9)") (class "Default")
      (node (ref "U$1") (pin "9") (pinfunction "9_9") (pintype "bidirectional"))
    )
    (net (code "78") (name "unconnected-(U$1-Pad16)") (class "Default")
      (node (ref "U$1") (pin "16") (pinfunction "16_16") (pintype "bidirectional"))
    )
    (net (code "79") (name "unconnected-(U$1-Pad17)") (class "Default")
      (node (ref "U$1") (pin "17") (pinfunction "17_17") (pintype "bidirectional"))
    )
    (net (code "80") (name "unconnected-(U$1-Pad22)") (class "Default")
      (node (ref "U$1") (pin "22") (pinfunction "22_22") (pintype "bidirectional"))
    )
    (net (code "81") (name "unconnected-(U$1-Pad23)") (class "Default")
      (node (ref "U$1") (pin "23") (pinfunction "23_23") (pintype "bidirectional"))
    )
    (net (code "82") (name "unconnected-(U$1-Pad24)") (class "Default")
      (node (ref "U$1") (pin "24") (pinfunction "24_24") (pintype "bidirectional"))
    )
    (net (code "83") (name "unconnected-(U$1-Pad25)") (class "Default")
      (node (ref "U$1") (pin "25") (pinfunction "25_25") (pintype "bidirectional"))
    )
    (net (code "84") (name "unconnected-(U$1-Pad26)") (class "Default")
      (node (ref "U$1") (pin "26") (pinfunction "26_26") (pintype "bidirectional"))
    )
    (net (code "85") (name "unconnected-(U$1-Pad38)") (class "Default")
      (node (ref "U$1") (pin "38") (pinfunction "38_38") (pintype "bidirectional"))
    )
    (net (code "86") (name "unconnected-(U$1-Pad40)") (class "Default")
      (node (ref "U$1") (pin "40") (pinfunction "40_40") (pintype "bidirectional"))
    )
    (net (code "87") (name "unconnected-(U$3-GPIN0-Pad26)") (class "Default")
      (node (ref "U$3") (pin "26") (pinfunction "GPIN0_26") (pintype "input"))
    )
    (net (code "88") (name "unconnected-(U$3-GPIN1-Pad27)") (class "Default")
      (node (ref "U$3") (pin "27") (pinfunction "GPIN1_27") (pintype "input"))
    )
    (net (code "89") (name "unconnected-(U$3-GPIN2-Pad28)") (class "Default")
      (node (ref "U$3") (pin "28") (pinfunction "GPIN2_28") (pintype "input"))
    )
    (net (code "90") (name "unconnected-(U$3-GPIN3-Pad29)") (class "Default")
      (node (ref "U$3") (pin "29") (pinfunction "GPIN3_29") (pintype "input"))
    )
    (net (code "91") (name "unconnected-(U$3-GPIN4-Pad30)") (class "Default")
      (node (ref "U$3") (pin "30") (pinfunction "GPIN4_30") (pintype "input"))
    )
    (net (code "92") (name "unconnected-(U$3-GPIN5-Pad31)") (class "Default")
      (node (ref "U$3") (pin "31") (pinfunction "GPIN5_31") (pintype "input"))
    )
    (net (code "93") (name "unconnected-(U$3-GPIN6-Pad32)") (class "Default")
      (node (ref "U$3") (pin "32") (pinfunction "GPIN6_32") (pintype "input"))
    )
    (net (code "94") (name "unconnected-(U$3-GPOUT1-Pad5)") (class "Default")
      (node (ref "U$3") (pin "5") (pinfunction "GPOUT1_5") (pintype "output"))
    )
    (net (code "95") (name "unconnected-(U$3-GPOUT2-Pad6)") (class "Default")
      (node (ref "U$3") (pin "6") (pinfunction "GPOUT2_6") (pintype "output"))
    )
    (net (code "96") (name "unconnected-(U$3-GPOUT3-Pad7)") (class "Default")
      (node (ref "U$3") (pin "7") (pinfunction "GPOUT3_7") (pintype "output"))
    )
    (net (code "97") (name "unconnected-(U$3-GPOUT4-Pad8)") (class "Default")
      (node (ref "U$3") (pin "8") (pinfunction "GPOUT4_8") (pintype "output"))
    )
    (net (code "98") (name "unconnected-(U$3-GPOUT5-Pad9)") (class "Default")
      (node (ref "U$3") (pin "9") (pinfunction "GPOUT5_9") (pintype "output"))
    )
    (net (code "99") (name "unconnected-(U$4-SO-Pad13)") (class "Default")
      (node (ref "U$4") (pin "13") (pinfunction "SO_13") (pintype "bidirectional"))
    )
    (net (code "100") (name "unconnected-(U$11-SO-Pad13)") (class "Default")
      (node (ref "U$11") (pin "13") (pinfunction "SO_13") (pintype "bidirectional"))
    )
  )
)
